# Mini_DDS.net
KiCad netlist of a schematic drawn in EAGLE
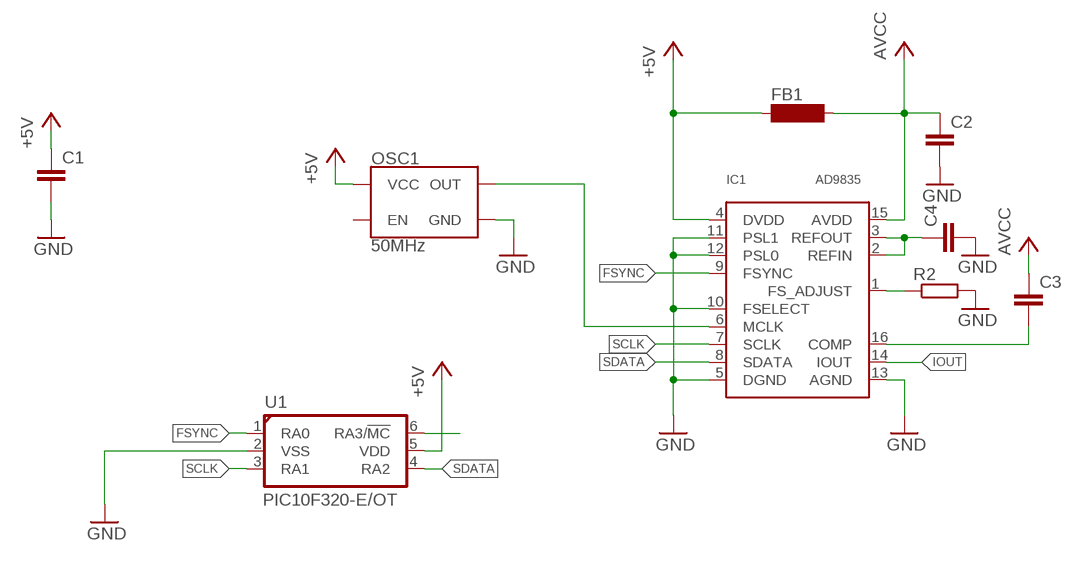
[diagram p0: schematic, sheet 1]

(export (version "E")
  (design (tool "Eeschema 10.0.6"))
  (components
    (comp (ref "C1")
      (value "C-EUC0603K")
      (footprint "eagle-import:C0603K")
      (libsource (lib "eagle-import") (part "C-EUC0603K"))
    )
    (comp (ref "C2")
      (value "C-EUC0603K")
      (footprint "eagle-import:C0603K")
      (libsource (lib "eagle-import") (part "C-EUC0603K"))
    )
    (comp (ref "C3")
      (value "C-EUC0603K")
      (footprint "eagle-import:C0603K")
      (libsource (lib "eagle-import") (part "C-EUC0603K"))
    )
    (comp (ref "C4")
      (value "C-EUC0603K")
      (footprint "eagle-import:C0603K")
      (libsource (lib "eagle-import") (part "C-EUC0603K"))
    )
    (comp (ref "FB1")
      (value "SM-1206")
      (footprint "eagle-import:SM-1206")
      (libsource (lib "eagle-import") (part "SM-1206"))
    )
    (comp (ref "IC1")
      (value "AD9835")
      (footprint "eagle-import:TSSOP16")
      (libsource (lib "eagle-import") (part "AD9835"))
    )
    (comp (ref "OSC1")
      (value "50MHz")
      (footprint "eagle-import:OSCILLATOR-SMD-7X5-4PAD")
      (libsource (lib "eagle-import") (part "OSCILLATORSMD-7X5-4PAD"))
    )
    (comp (ref "R2")
      (value "R-EU_R0603")
      (footprint "eagle-import:R0603")
      (libsource (lib "eagle-import") (part "R-EU_R0603"))
    )
    (comp (ref "U1")
      (value "PIC10F320-E/OT")
      (footprint "eagle-import:SOT23-6L")
      (libsource (lib "eagle-import") (part "PIC10F320OT"))
    )
  )
  (nets
    (net (code "1") (name "+5V") (class "Default")
      (node (ref "C1") (pin "1") (pinfunction "1_1") (pintype "passive"))
      (node (ref "FB1") (pin "1") (pinfunction "1_1") (pintype "passive"))
      (node (ref "IC1") (pin "4") (pinfunction "DVDD_4") (pintype "power_in"))
      (node (ref "OSC1") (pin "4") (pinfunction "VCC_4") (pintype "bidirectional"))
      (node (ref "U1") (pin "5") (pinfunction "VDD_5") (pintype "passive"))
    )
    (net (code "2") (name "AVCC") (class "Default")
      (node (ref "C2") (pin "1") (pinfunction "1_1") (pintype "passive"))
      (node (ref "C3") (pin "1") (pinfunction "1_1") (pintype "passive"))
      (node (ref "FB1") (pin "2") (pinfunction "2_2") (pintype "passive"))
      (node (ref "IC1") (pin "15") (pinfunction "AVDD_15") (pintype "power_in"))
    )
    (net (code "3") (name "FSYNC") (class "Default")
      (node (ref "IC1") (pin "9") (pinfunction "FSYNC_9") (pintype "bidirectional"))
      (node (ref "U1") (pin "1") (pinfunction "RA0_1") (pintype "bidirectional"))
    )
    (net (code "4") (name "GND") (class "Default")
      (node (ref "C1") (pin "2") (pinfunction "2_2") (pintype "passive"))
      (node (ref "C2") (pin "2") (pinfunction "2_2") (pintype "passive"))
      (node (ref "C4") (pin "2") (pinfunction "2_2") (pintype "passive"))
      (node (ref "IC1") (pin "10") (pinfunction "FSELECT_10") (pintype "bidirectional"))
      (node (ref "IC1") (pin "11") (pinfunction "PSL1_11") (pintype "bidirectional"))
      (node (ref "IC1") (pin "12") (pinfunction "PSL0_12") (pintype "bidirectional"))
      (node (ref "IC1") (pin "13") (pinfunction "AGND_13") (pintype "power_in"))
      (node (ref "IC1") (pin "5") (pinfunction "DGND_5") (pintype "power_in"))
      (node (ref "OSC1") (pin "2") (pinfunction "GND_2") (pintype "bidirectional"))
      (node (ref "R2") (pin "2") (pinfunction "2_2") (pintype "passive"))
      (node (ref "U1") (pin "2") (pinfunction "VSS_2") (pintype "passive"))
    )
    (net (code "5") (name "IOUT") (class "Default")
      (node (ref "IC1") (pin "14") (pinfunction "IOUT_14") (pintype "bidirectional"))
    )
    (net (code "6") (name "Net-(IC1-COMP)") (class "Default")
      (node (ref "C3") (pin "2") (pinfunction "2_2") (pintype "passive"))
      (node (ref "IC1") (pin "16") (pinfunction "COMP_16") (pintype "bidirectional"))
    )
    (net (code "7") (name "Net-(IC1-FS_ADJUST)") (class "Default")
      (node (ref "IC1") (pin "1") (pinfunction "FS_ADJUST_1") (pintype "bidirectional"))
      (node (ref "R2") (pin "1") (pinfunction "1_1") (pintype "passive"))
    )
    (net (code "8") (name "Net-(IC1-MCLK)") (class "Default")
      (node (ref "IC1") (pin "6") (pinfunction "MCLK_6") (pintype "bidirectional"))
      (node (ref "OSC1") (pin "3") (pinfunction "OUT_3") (pintype "bidirectional"))
    )
    (net (code "9") (name "Net-(IC1-REFIN)") (class "Default")
      (node (ref "C4") (pin "1") (pinfunction "1_1") (pintype "passive"))
      (node (ref "IC1") (pin "2") (pinfunction "REFIN_2") (pintype "bidirectional"))
      (node (ref "IC1") (pin "3") (pinfunction "REFOUT_3") (pintype "bidirectional"))
    )
    (net (code "10") (name "SCLK") (class "Default")
      (node (ref "IC1") (pin "7") (pinfunction "SCLK_7") (pintype "bidirectional"))
      (node (ref "U1") (pin "3") (pinfunction "RA1_3") (pintype "bidirectional"))
    )
    (net (code "11") (name "SDATA") (class "Default")
      (node (ref "IC1") (pin "8") (pinfunction "SDATA_8") (pintype "bidirectional"))
      (node (ref "U1") (pin "4") (pinfunction "RA2_4") (pintype "bidirectional"))
    )
    (net (code "12") (name "unconnected-(OSC1-EN-Pad1)") (class "Default")
      (node (ref "OSC1") (pin "1") (pinfunction "EN_1") (pintype "bidirectional"))
    )
    (net (code "13") (name "unconnected-(U1-RA3{slash}~{MC}-Pad6)") (class "Default")
      (node (ref "U1") (pin "6") (pinfunction "RA3/~{MC}_6") (pintype "input"))
    )
  )
)
